# power_supply.net
KiCad netlist of a schematic drawn in Altium Designer
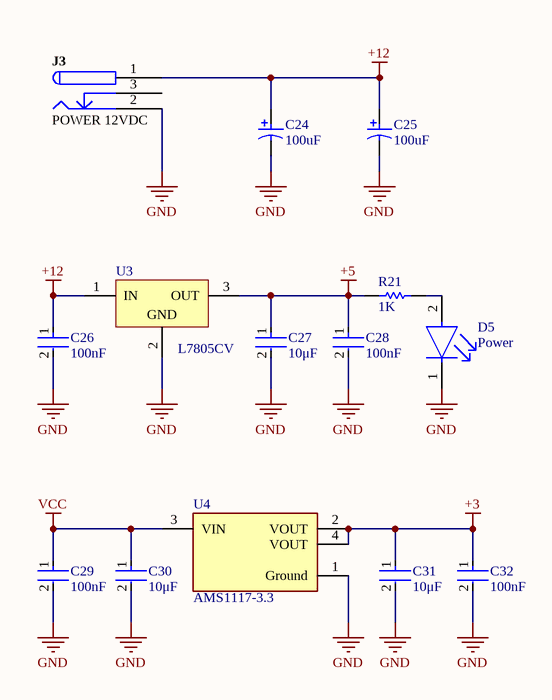
[diagram p0: power_supply.SchDoc]

(export (version "E")
  (design (tool "Eeschema 10.0.6"))
  (components
    (comp (ref "C24")
      (value "100uF")
      (footprint "PNSC-FK-V-D8_V")
      (fields (field (name "MANUFACTURER") "Panasonic"))
      (libsource (lib "Altium Content Vault") (part "CAP-P-2"))
    )
    (comp (ref "C25")
      (value "100uF")
      (footprint "PNSC-FK-V-D8_V")
      (fields (field (name "MANUFACTURER") "Panasonic"))
      (libsource (lib "Altium Content Vault") (part "CAP-P-2"))
    )
    (comp (ref "C26")
      (value "100nF")
      (footprint "FP-0603-L_1_6_0_15-W_0_81-IPC_A")
      (description "General Purpose Ceramic Capacitor, 0603, 100nF, 10%, X7R, 15%, 50V")
      (fields (field (name "TOLERANCE") "10%") (field (name "VOLTAGE") "50V"))
      (libsource (lib "Altium Content Vault") (part "02cd4be3c70576c341d710602a673aa"))
    )
    (comp (ref "C27")
      (value "10μF")
      (footprint "FP-0603-L_1_6_0_15-W_0_81-IPC_A")
      (description "General Purpose Ceramic Capacitor, 0603, 100nF, 10%, X7R, 15%, 50V")
      (fields (field (name "TOLERANCE") "10%") (field (name "VOLTAGE") "50V"))
      (libsource (lib "Altium Content Vault") (part "02cd4be3c70576c341d710602a673aa"))
    )
    (comp (ref "C28")
      (value "100nF")
      (footprint "FP-0603-L_1_6_0_15-W_0_81-IPC_A")
      (description "General Purpose Ceramic Capacitor, 0603, 100nF, 10%, X7R, 15%, 50V")
      (fields (field (name "TOLERANCE") "10%") (field (name "VOLTAGE") "50V"))
      (libsource (lib "Altium Content Vault") (part "02cd4be3c70576c341d710602a673aa"))
    )
    (comp (ref "C29")
      (value "100nF")
      (footprint "FP-0603-L_1_6_0_15-W_0_81-IPC_A")
      (description "General Purpose Ceramic Capacitor, 0603, 100nF, 10%, X7R, 15%, 50V")
      (fields (field (name "TOLERANCE") "10%") (field (name "VOLTAGE") "50V"))
      (libsource (lib "Altium Content Vault") (part "02cd4be3c70576c341d710602a673aa"))
    )
    (comp (ref "C30")
      (value "10μF")
      (footprint "FP-0603-L_1_6_0_15-W_0_81-IPC_A")
      (description "General Purpose Ceramic Capacitor, 0603, 100nF, 10%, X7R, 15%, 50V")
      (fields (field (name "TOLERANCE") "10%") (field (name "VOLTAGE") "50V"))
      (libsource (lib "Altium Content Vault") (part "02cd4be3c70576c341d710602a673aa"))
    )
    (comp (ref "C31")
      (value "10μF")
      (footprint "FP-0603-L_1_6_0_15-W_0_81-IPC_A")
      (description "General Purpose Ceramic Capacitor, 0603, 100nF, 10%, X7R, 15%, 50V")
      (fields (field (name "TOLERANCE") "10%") (field (name "VOLTAGE") "50V"))
      (libsource (lib "Altium Content Vault") (part "02cd4be3c70576c341d710602a673aa"))
    )
    (comp (ref "C32")
      (value "100nF")
      (footprint "FP-0603-L_1_6_0_15-W_0_81-IPC_A")
      (description "General Purpose Ceramic Capacitor, 0603, 100nF, 10%, X7R, 15%, 50V")
      (fields (field (name "TOLERANCE") "10%") (field (name "VOLTAGE") "50V"))
      (libsource (lib "Altium Content Vault") (part "02cd4be3c70576c341d710602a673aa"))
    )
    (comp (ref "D5")
      (value "Power")
      (footprint "FP-HLMP-4700-MFG")
      (description "LED RED DIFFUSED T-1 3/4 T/H")
      (fields
        (field (name "OCTOPART") "https://octopart.com/hlmp-4700-broadcom-71130526")
        (field (name "MANUFACTURER") "Broadcom")
      )
      (libsource (lib "Altium Content Vault") (part "8706943c75ba83719d021d2fdc84c58"))
    )
    (comp (ref "J3")
      (value "POWER 12VDC")
      (footprint "KYCN-KLDX-0202-B_V")
      (description "3 Conductor Power Jack, 2 break 2 aux contacts")
      (fields (field (name "PARTNUMBER") "KLDX-0202-B"))
      (libsource (lib "Altium Content Vault") (part "KYCN-KLDX-0202-B-3"))
    )
    (comp (ref "R21")
      (value "1K")
      (footprint "RESC1609X55X30ML15T15")
      (description "Chip Resistor, 10 KOhm, +/- 1%, 0.1 W, -55 to 155 degC, 0603 (1608 Metric), RoHS, Tape and Reel")
      (fields (field (name "TOLERANCE") "1%") (field (name "MANUFACTURER") "Panasonic"))
      (libsource (lib "Altium Content Vault") (part "RES-2"))
    )
    (comp (ref "U3")
      (value "L7805CV")
      (footprint "TO220")
      (description "Positive Voltage Regulator, 5V, 3-Pin TO-220")
      (libsource (lib "Altium Content Vault") (part "PM-REG-L4940-SIL3"))
    )
    (comp (ref "U4")
      (value "AMS1117-3.3")
      (footprint "FP-AMS1117-IPC_A")
      (description "LDO Voltage Regulators 1A, 3.3V")
      (fields
        (field (name "OCTOPART") "https://octopart.com/ams1117-3.3-advanced+monolithic+systems-25899300")
        (field (name "MANUFACTURER") "Advanced Monolithic Systems")
      )
      (libsource (lib "Altium Content Vault") (part "8bdbb5f8e77002000e30dd2845d0354"))
    )
  )
  (nets
    (net (code "1") (name "+3") (class "Default")
      (node (ref "C31") (pin "1") (pinfunction "1_1") (pintype "passive"))
      (node (ref "C32") (pin "1") (pinfunction "1_1") (pintype "passive"))
      (node (ref "U4") (pin "2") (pinfunction "VOUT_2") (pintype "passive"))
      (node (ref "U4") (pin "4") (pinfunction "VOUT_4") (pintype "passive"))
    )
    (net (code "2") (name "+5") (class "Default")
      (node (ref "C27") (pin "1") (pinfunction "1_1") (pintype "passive"))
      (node (ref "C28") (pin "1") (pinfunction "1_1") (pintype "passive"))
      (node (ref "R21") (pin "2") (pinfunction "2_2") (pintype "passive"))
      (node (ref "U3") (pin "3") (pinfunction "OUT_3") (pintype "power_in"))
    )
    (net (code "3") (name "+12") (class "Default")
      (node (ref "C24") (pin "1") (pinfunction "1_1") (pintype "passive"))
      (node (ref "C25") (pin "1") (pinfunction "1_1") (pintype "passive"))
      (node (ref "C26") (pin "1") (pinfunction "1_1") (pintype "passive"))
      (node (ref "J3") (pin "1") (pintype "power_in"))
      (node (ref "U3") (pin "1") (pinfunction "IN_1") (pintype "power_in"))
    )
    (net (code "4") (name "GND") (class "Default")
      (node (ref "C24") (pin "2") (pinfunction "2_2") (pintype "passive"))
      (node (ref "C25") (pin "2") (pinfunction "2_2") (pintype "passive"))
      (node (ref "C26") (pin "2") (pinfunction "2_2") (pintype "passive"))
      (node (ref "C27") (pin "2") (pinfunction "2_2") (pintype "passive"))
      (node (ref "C28") (pin "2") (pinfunction "2_2") (pintype "passive"))
      (node (ref "C29") (pin "2") (pinfunction "2_2") (pintype "passive"))
      (node (ref "C30") (pin "2") (pinfunction "2_2") (pintype "passive"))
      (node (ref "C31") (pin "2") (pinfunction "2_2") (pintype "passive"))
      (node (ref "C32") (pin "2") (pinfunction "2_2") (pintype "passive"))
      (node (ref "D5") (pin "1") (pinfunction "C_1") (pintype "passive"))
      (node (ref "J3") (pin "2") (pintype "power_in"))
      (node (ref "U3") (pin "2") (pinfunction "GND_2") (pintype "power_in"))
      (node (ref "U4") (pin "1") (pinfunction "Ground_1") (pintype "power_in"))
    )
    (net (code "5") (name "Net-(D5-A)") (class "Default")
      (node (ref "D5") (pin "2") (pinfunction "A_2") (pintype "passive"))
      (node (ref "R21") (pin "1") (pinfunction "1_1") (pintype "passive"))
    )
    (net (code "6") (name "VCC") (class "Default")
      (node (ref "C29") (pin "1") (pinfunction "1_1") (pintype "passive"))
      (node (ref "C30") (pin "1") (pinfunction "1_1") (pintype "passive"))
      (node (ref "U4") (pin "3") (pinfunction "VIN_3") (pintype "power_in"))
    )
    (net (code "7") (name "unconnected-(J3-Pad3)") (class "Default")
      (node (ref "J3") (pin "3") (pintype "power_in"))
    )
  )
)
